# nes_snes_simple.net
KiCad netlist of a schematic drawn in EAGLE
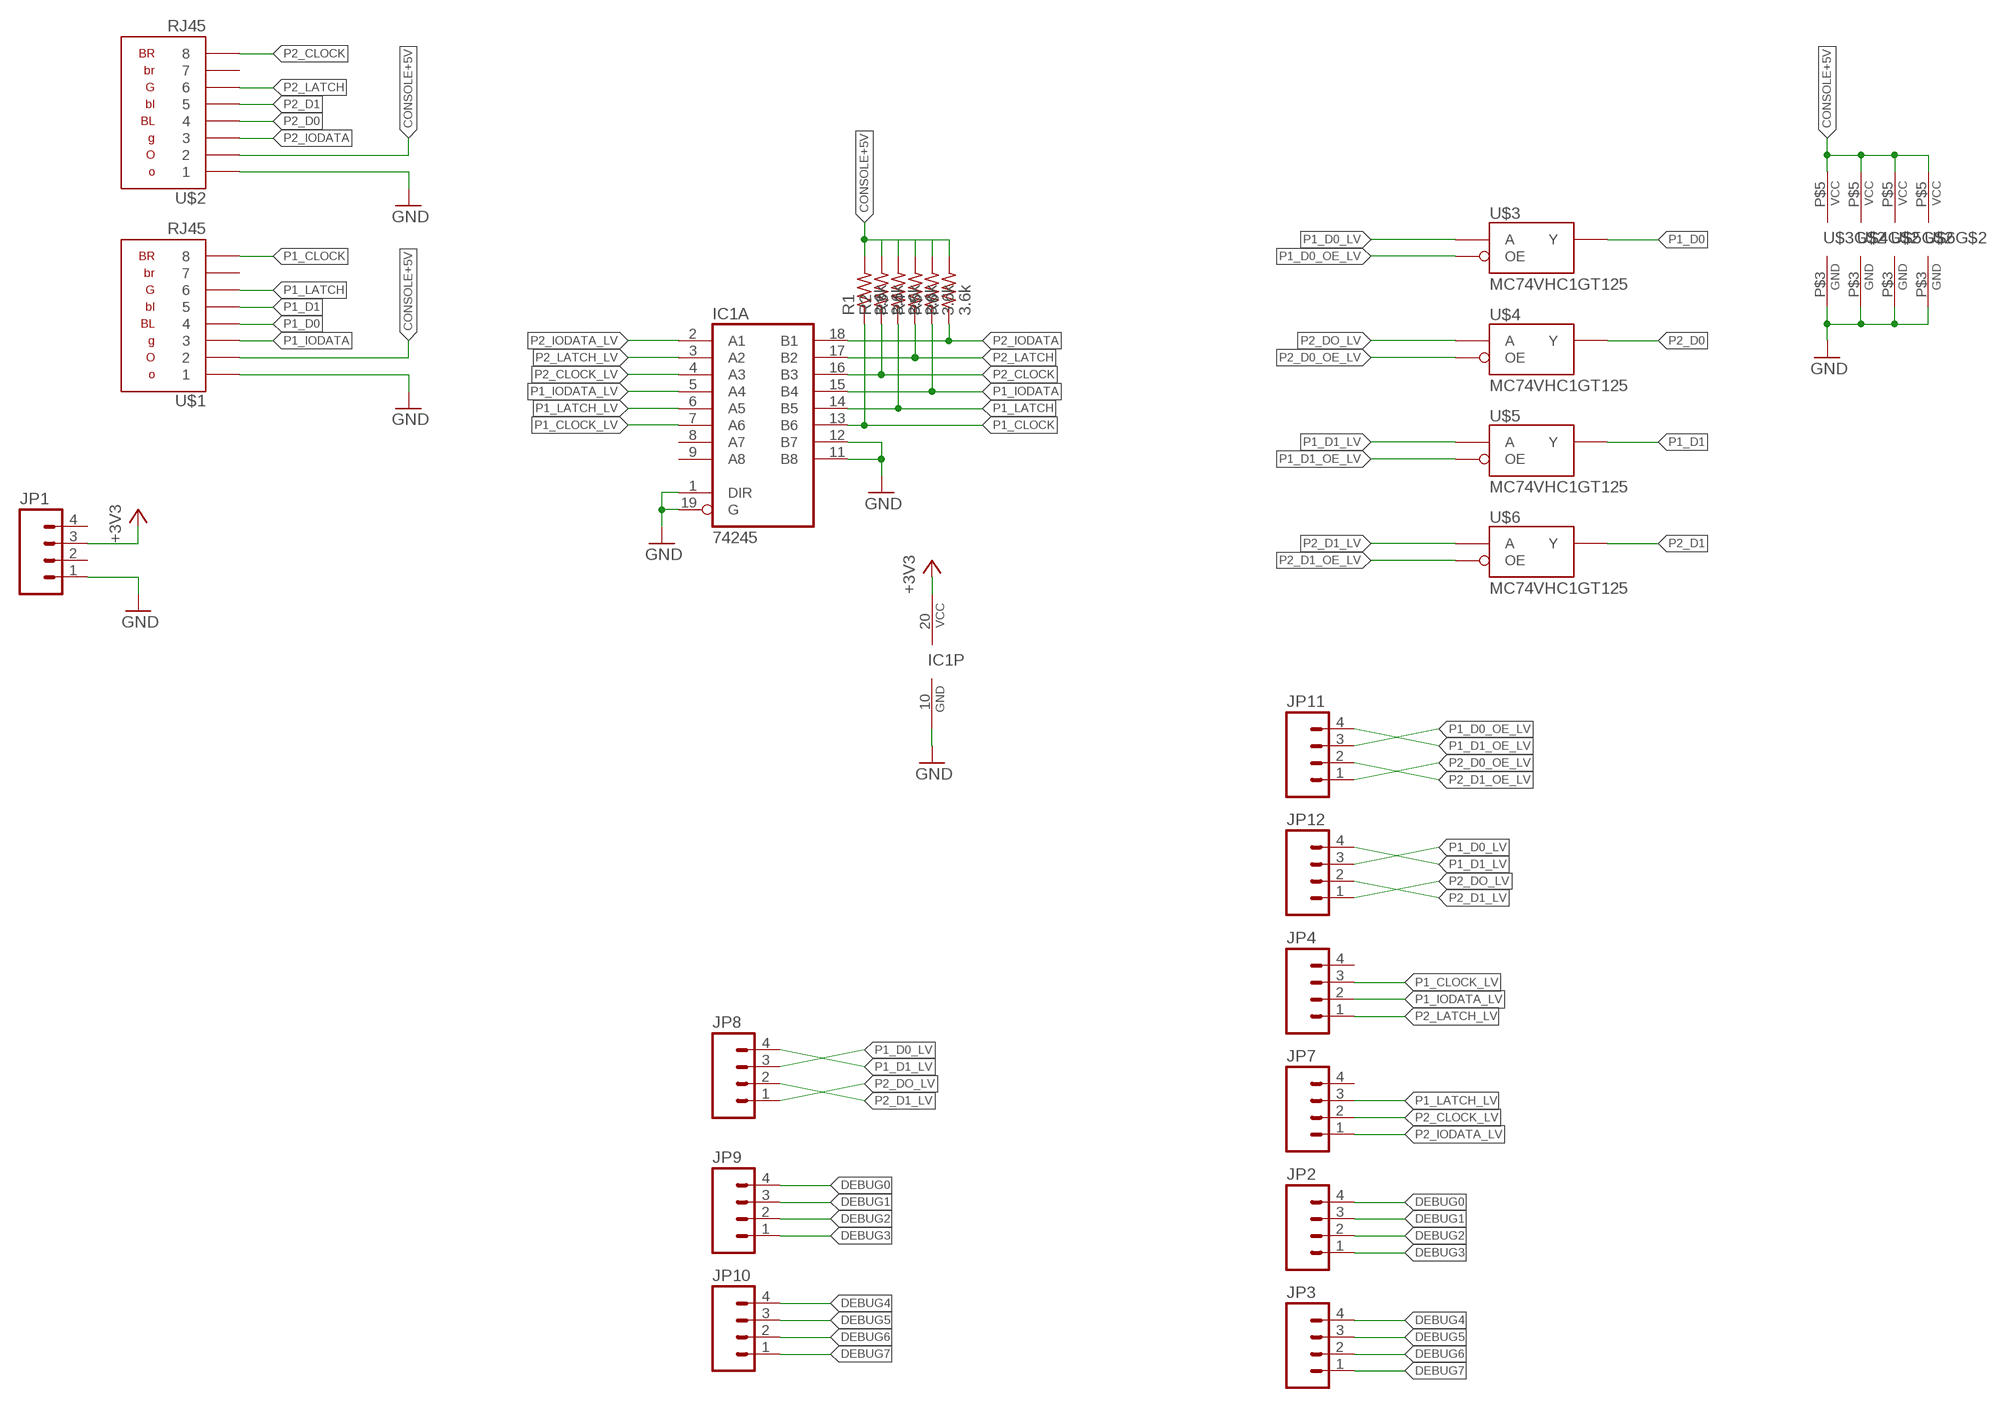
[diagram p0: schematic, sheet 1]

(export (version "E")
  (design (tool "Eeschema 10.0.6"))
  (components
    (comp (ref "IC1")
      (value "74245")
      (footprint "eagle-import:DIL20")
      (libsource (lib "eagle-import") (part "74245"))
    )
    (comp (ref "JP1")
      (value "M04PTH")
      (footprint "eagle-import:1X04")
      (libsource (lib "eagle-import") (part "M04PTH"))
    )
    (comp (ref "JP2")
      (value "M04PTH")
      (footprint "eagle-import:1X04")
      (libsource (lib "eagle-import") (part "M04PTH"))
    )
    (comp (ref "JP3")
      (value "M04PTH")
      (footprint "eagle-import:1X04")
      (libsource (lib "eagle-import") (part "M04PTH"))
    )
    (comp (ref "JP4")
      (value "M04PTH")
      (footprint "eagle-import:1X04")
      (libsource (lib "eagle-import") (part "M04PTH"))
    )
    (comp (ref "JP7")
      (value "M04PTH")
      (footprint "eagle-import:1X04")
      (libsource (lib "eagle-import") (part "M04PTH"))
    )
    (comp (ref "JP8")
      (value "M04PTH")
      (footprint "eagle-import:1X04")
      (libsource (lib "eagle-import") (part "M04PTH"))
    )
    (comp (ref "JP9")
      (value "M04PTH")
      (footprint "eagle-import:1X04")
      (libsource (lib "eagle-import") (part "M04PTH"))
    )
    (comp (ref "JP10")
      (value "M04PTH")
      (footprint "eagle-import:1X04")
      (libsource (lib "eagle-import") (part "M04PTH"))
    )
    (comp (ref "JP11")
      (value "M04PTH")
      (footprint "eagle-import:1X04")
      (libsource (lib "eagle-import") (part "M04PTH"))
    )
    (comp (ref "JP12")
      (value "M04PTH")
      (footprint "eagle-import:1X04")
      (libsource (lib "eagle-import") (part "M04PTH"))
    )
    (comp (ref "R1")
      (value "3.6k")
      (footprint "eagle-import:0207_2V")
      (libsource (lib "eagle-import") (part "R-US_0207/2V"))
    )
    (comp (ref "R2")
      (value "3.6k")
      (footprint "eagle-import:0207_2V")
      (libsource (lib "eagle-import") (part "R-US_0207/2V"))
    )
    (comp (ref "R3")
      (value "3.6k")
      (footprint "eagle-import:0207_2V")
      (libsource (lib "eagle-import") (part "R-US_0207/2V"))
    )
    (comp (ref "R4")
      (value "3.6k")
      (footprint "eagle-import:0207_2V")
      (libsource (lib "eagle-import") (part "R-US_0207/2V"))
    )
    (comp (ref "R5")
      (value "3.6k")
      (footprint "eagle-import:0207_2V")
      (libsource (lib "eagle-import") (part "R-US_0207/2V"))
    )
    (comp (ref "R6")
      (value "3.6k")
      (footprint "eagle-import:0207_2V")
      (libsource (lib "eagle-import") (part "R-US_0207/2V"))
    )
    (comp (ref "U$1")
      (value "RJ45")
      (footprint "eagle-import:RJ45")
      (libsource (lib "eagle-import") (part "RJ45"))
    )
    (comp (ref "U$2")
      (value "RJ45")
      (footprint "eagle-import:RJ45")
      (libsource (lib "eagle-import") (part "RJ45"))
    )
    (comp (ref "U$3")
      (value "MC74VHC1GT125")
      (footprint "eagle-import:TSOP-5")
      (libsource (lib "eagle-import") (part "MC74VHC1GT125"))
    )
    (comp (ref "U$4")
      (value "MC74VHC1GT125")
      (footprint "eagle-import:TSOP-5")
      (libsource (lib "eagle-import") (part "MC74VHC1GT125"))
    )
    (comp (ref "U$5")
      (value "MC74VHC1GT125")
      (footprint "eagle-import:TSOP-5")
      (libsource (lib "eagle-import") (part "MC74VHC1GT125"))
    )
    (comp (ref "U$6")
      (value "MC74VHC1GT125")
      (footprint "eagle-import:TSOP-5")
      (libsource (lib "eagle-import") (part "MC74VHC1GT125"))
    )
  )
  (nets
    (net (code "1") (name "+3V3") (class "Default")
      (node (ref "IC1") (pin "20") (pinfunction "VCC_20") (pintype "power_in"))
      (node (ref "JP1") (pin "3") (pinfunction "3_3") (pintype "passive"))
    )
    (net (code "2") (name "CONSOLE+5V") (class "Default")
      (node (ref "R1") (pin "2") (pinfunction "2_2") (pintype "passive"))
      (node (ref "R2") (pin "2") (pinfunction "2_2") (pintype "passive"))
      (node (ref "R3") (pin "2") (pinfunction "2_2") (pintype "passive"))
      (node (ref "R4") (pin "2") (pinfunction "2_2") (pintype "passive"))
      (node (ref "R5") (pin "2") (pinfunction "2_2") (pintype "passive"))
      (node (ref "R6") (pin "2") (pinfunction "2_2") (pintype "passive"))
      (node (ref "U$1") (pin "2") (pinfunction "2_2") (pintype "bidirectional"))
      (node (ref "U$2") (pin "2") (pinfunction "2_2") (pintype "bidirectional"))
      (node (ref "U$3") (pin "P$5") (pinfunction "VCC_P$5") (pintype "power_in"))
      (node (ref "U$4") (pin "P$5") (pinfunction "VCC_P$5") (pintype "power_in"))
      (node (ref "U$5") (pin "P$5") (pinfunction "VCC_P$5") (pintype "power_in"))
      (node (ref "U$6") (pin "P$5") (pinfunction "VCC_P$5") (pintype "power_in"))
    )
    (net (code "3") (name "DEBUG0") (class "Default")
      (node (ref "JP2") (pin "4") (pinfunction "4_4") (pintype "passive"))
      (node (ref "JP9") (pin "4") (pinfunction "4_4") (pintype "passive"))
    )
    (net (code "4") (name "DEBUG1") (class "Default")
      (node (ref "JP2") (pin "3") (pinfunction "3_3") (pintype "passive"))
      (node (ref "JP9") (pin "3") (pinfunction "3_3") (pintype "passive"))
    )
    (net (code "5") (name "DEBUG2") (class "Default")
      (node (ref "JP2") (pin "2") (pinfunction "2_2") (pintype "passive"))
      (node (ref "JP9") (pin "2") (pinfunction "2_2") (pintype "passive"))
    )
    (net (code "6") (name "DEBUG3") (class "Default")
      (node (ref "JP2") (pin "1") (pinfunction "1_1") (pintype "passive"))
      (node (ref "JP9") (pin "1") (pinfunction "1_1") (pintype "passive"))
    )
    (net (code "7") (name "DEBUG4") (class "Default")
      (node (ref "JP10") (pin "4") (pinfunction "4_4") (pintype "passive"))
      (node (ref "JP3") (pin "4") (pinfunction "4_4") (pintype "passive"))
    )
    (net (code "8") (name "DEBUG5") (class "Default")
      (node (ref "JP10") (pin "3") (pinfunction "3_3") (pintype "passive"))
      (node (ref "JP3") (pin "3") (pinfunction "3_3") (pintype "passive"))
    )
    (net (code "9") (name "DEBUG6") (class "Default")
      (node (ref "JP10") (pin "2") (pinfunction "2_2") (pintype "passive"))
      (node (ref "JP3") (pin "2") (pinfunction "2_2") (pintype "passive"))
    )
    (net (code "10") (name "DEBUG7") (class "Default")
      (node (ref "JP10") (pin "1") (pinfunction "1_1") (pintype "passive"))
      (node (ref "JP3") (pin "1") (pinfunction "1_1") (pintype "passive"))
    )
    (net (code "11") (name "GND") (class "Default")
      (node (ref "IC1") (pin "1") (pinfunction "DIR_1") (pintype "input"))
      (node (ref "IC1") (pin "10") (pinfunction "GND_10") (pintype "power_in"))
      (node (ref "IC1") (pin "11") (pinfunction "B8_11") (pintype "bidirectional"))
      (node (ref "IC1") (pin "12") (pinfunction "B7_12") (pintype "bidirectional"))
      (node (ref "IC1") (pin "19") (pinfunction "G_19") (pintype "input"))
      (node (ref "JP1") (pin "1") (pinfunction "1_1") (pintype "passive"))
      (node (ref "U$1") (pin "1") (pinfunction "1_1") (pintype "bidirectional"))
      (node (ref "U$2") (pin "1") (pinfunction "1_1") (pintype "bidirectional"))
      (node (ref "U$3") (pin "P$3") (pinfunction "GND_P$3") (pintype "power_in"))
      (node (ref "U$4") (pin "P$3") (pinfunction "GND_P$3") (pintype "power_in"))
      (node (ref "U$5") (pin "P$3") (pinfunction "GND_P$3") (pintype "power_in"))
      (node (ref "U$6") (pin "P$3") (pinfunction "GND_P$3") (pintype "power_in"))
    )
    (net (code "12") (name "P1_CLOCK") (class "Default")
      (node (ref "IC1") (pin "13") (pinfunction "B6_13") (pintype "bidirectional"))
      (node (ref "R1") (pin "1") (pinfunction "1_1") (pintype "passive"))
      (node (ref "U$1") (pin "8") (pinfunction "8_8") (pintype "bidirectional"))
    )
    (net (code "13") (name "P1_CLOCK_LV") (class "Default")
      (node (ref "IC1") (pin "7") (pinfunction "A6_7") (pintype "bidirectional"))
      (node (ref "JP4") (pin "3") (pinfunction "3_3") (pintype "passive"))
    )
    (net (code "14") (name "P1_D0") (class "Default")
      (node (ref "U$1") (pin "4") (pinfunction "4_4") (pintype "bidirectional"))
      (node (ref "U$3") (pin "P$4") (pinfunction "Y_P$4") (pintype "bidirectional"))
    )
    (net (code "15") (name "P1_D0_LV") (class "Default")
      (node (ref "JP12") (pin "3") (pinfunction "3_3") (pintype "passive"))
      (node (ref "JP8") (pin "3") (pinfunction "3_3") (pintype "passive"))
      (node (ref "U$3") (pin "P$2") (pinfunction "A_P$2") (pintype "bidirectional"))
    )
    (net (code "16") (name "P1_D0_OE_LV") (class "Default")
      (node (ref "JP11") (pin "3") (pinfunction "3_3") (pintype "passive"))
      (node (ref "U$3") (pin "P$1") (pinfunction "OE_P$1") (pintype "bidirectional"))
    )
    (net (code "17") (name "P1_D1") (class "Default")
      (node (ref "U$1") (pin "5") (pinfunction "5_5") (pintype "bidirectional"))
      (node (ref "U$5") (pin "P$4") (pinfunction "Y_P$4") (pintype "bidirectional"))
    )
    (net (code "18") (name "P1_D1_LV") (class "Default")
      (node (ref "JP12") (pin "4") (pinfunction "4_4") (pintype "passive"))
      (node (ref "JP8") (pin "4") (pinfunction "4_4") (pintype "passive"))
      (node (ref "U$5") (pin "P$2") (pinfunction "A_P$2") (pintype "bidirectional"))
    )
    (net (code "19") (name "P1_D1_OE_LV") (class "Default")
      (node (ref "JP11") (pin "4") (pinfunction "4_4") (pintype "passive"))
      (node (ref "U$5") (pin "P$1") (pinfunction "OE_P$1") (pintype "bidirectional"))
    )
    (net (code "20") (name "P1_IODATA") (class "Default")
      (node (ref "IC1") (pin "15") (pinfunction "B4_15") (pintype "bidirectional"))
      (node (ref "R5") (pin "1") (pinfunction "1_1") (pintype "passive"))
      (node (ref "U$1") (pin "3") (pinfunction "3_3") (pintype "bidirectional"))
    )
    (net (code "21") (name "P1_IODATA_LV") (class "Default")
      (node (ref "IC1") (pin "5") (pinfunction "A4_5") (pintype "bidirectional"))
      (node (ref "JP4") (pin "2") (pinfunction "2_2") (pintype "passive"))
    )
    (net (code "22") (name "P1_LATCH") (class "Default")
      (node (ref "IC1") (pin "14") (pinfunction "B5_14") (pintype "bidirectional"))
      (node (ref "R3") (pin "1") (pinfunction "1_1") (pintype "passive"))
      (node (ref "U$1") (pin "6") (pinfunction "6_6") (pintype "bidirectional"))
    )
    (net (code "23") (name "P1_LATCH_LV") (class "Default")
      (node (ref "IC1") (pin "6") (pinfunction "A5_6") (pintype "bidirectional"))
      (node (ref "JP7") (pin "3") (pinfunction "3_3") (pintype "passive"))
    )
    (net (code "24") (name "P2_CLOCK") (class "Default")
      (node (ref "IC1") (pin "16") (pinfunction "B3_16") (pintype "bidirectional"))
      (node (ref "R2") (pin "1") (pinfunction "1_1") (pintype "passive"))
      (node (ref "U$2") (pin "8") (pinfunction "8_8") (pintype "bidirectional"))
    )
    (net (code "25") (name "P2_CLOCK_LV") (class "Default")
      (node (ref "IC1") (pin "4") (pinfunction "A3_4") (pintype "bidirectional"))
      (node (ref "JP7") (pin "2") (pinfunction "2_2") (pintype "passive"))
    )
    (net (code "26") (name "P2_D0") (class "Default")
      (node (ref "U$2") (pin "4") (pinfunction "4_4") (pintype "bidirectional"))
      (node (ref "U$4") (pin "P$4") (pinfunction "Y_P$4") (pintype "bidirectional"))
    )
    (net (code "27") (name "P2_D0_OE_LV") (class "Default")
      (node (ref "JP11") (pin "1") (pinfunction "1_1") (pintype "passive"))
      (node (ref "U$4") (pin "P$1") (pinfunction "OE_P$1") (pintype "bidirectional"))
    )
    (net (code "28") (name "P2_D1") (class "Default")
      (node (ref "U$2") (pin "5") (pinfunction "5_5") (pintype "bidirectional"))
      (node (ref "U$6") (pin "P$4") (pinfunction "Y_P$4") (pintype "bidirectional"))
    )
    (net (code "29") (name "P2_D1_LV") (class "Default")
      (node (ref "JP12") (pin "2") (pinfunction "2_2") (pintype "passive"))
      (node (ref "JP8") (pin "2") (pinfunction "2_2") (pintype "passive"))
      (node (ref "U$6") (pin "P$2") (pinfunction "A_P$2") (pintype "bidirectional"))
    )
    (net (code "30") (name "P2_D1_OE_LV") (class "Default")
      (node (ref "JP11") (pin "2") (pinfunction "2_2") (pintype "passive"))
      (node (ref "U$6") (pin "P$1") (pinfunction "OE_P$1") (pintype "bidirectional"))
    )
    (net (code "31") (name "P2_DO_LV") (class "Default")
      (node (ref "JP12") (pin "1") (pinfunction "1_1") (pintype "passive"))
      (node (ref "JP8") (pin "1") (pinfunction "1_1") (pintype "passive"))
      (node (ref "U$4") (pin "P$2") (pinfunction "A_P$2") (pintype "bidirectional"))
    )
    (net (code "32") (name "P2_IODATA") (class "Default")
      (node (ref "IC1") (pin "18") (pinfunction "B1_18") (pintype "bidirectional"))
      (node (ref "R6") (pin "1") (pinfunction "1_1") (pintype "passive"))
      (node (ref "U$2") (pin "3") (pinfunction "3_3") (pintype "bidirectional"))
    )
    (net (code "33") (name "P2_IODATA_LV") (class "Default")
      (node (ref "IC1") (pin "2") (pinfunction "A1_2") (pintype "bidirectional"))
      (node (ref "JP7") (pin "1") (pinfunction "1_1") (pintype "passive"))
    )
    (net (code "34") (name "P2_LATCH") (class "Default")
      (node (ref "IC1") (pin "17") (pinfunction "B2_17") (pintype "bidirectional"))
      (node (ref "R4") (pin "1") (pinfunction "1_1") (pintype "passive"))
      (node (ref "U$2") (pin "6") (pinfunction "6_6") (pintype "bidirectional"))
    )
    (net (code "35") (name "P2_LATCH_LV") (class "Default")
      (node (ref "IC1") (pin "3") (pinfunction "A2_3") (pintype "bidirectional"))
      (node (ref "JP4") (pin "1") (pinfunction "1_1") (pintype "passive"))
    )
    (net (code "36") (name "unconnected-(IC1A-A7-Pad8)") (class "Default")
      (node (ref "IC1") (pin "8") (pinfunction "A7_8") (pintype "bidirectional"))
    )
    (net (code "37") (name "unconnected-(IC1A-A8-Pad9)") (class "Default")
      (node (ref "IC1") (pin "9") (pinfunction "A8_9") (pintype "bidirectional"))
    )
    (net (code "38") (name "unconnected-(JP1-Pad2)") (class "Default")
      (node (ref "JP1") (pin "2") (pinfunction "2_2") (pintype "passive"))
    )
    (net (code "39") (name "unconnected-(JP1-Pad4)") (class "Default")
      (node (ref "JP1") (pin "4") (pinfunction "4_4") (pintype "passive"))
    )
    (net (code "40") (name "unconnected-(JP4-Pad4)") (class "Default")
      (node (ref "JP4") (pin "4") (pinfunction "4_4") (pintype "passive"))
    )
    (net (code "41") (name "unconnected-(JP7-Pad4)") (class "Default")
      (node (ref "JP7") (pin "4") (pinfunction "4_4") (pintype "passive"))
    )
    (net (code "42") (name "unconnected-(U$1-Pad7)") (class "Default")
      (node (ref "U$1") (pin "7") (pinfunction "7_7") (pintype "bidirectional"))
    )
    (net (code "43") (name "unconnected-(U$2-Pad7)") (class "Default")
      (node (ref "U$2") (pin "7") (pinfunction "7_7") (pintype "bidirectional"))
    )
  )
)
